# Audio_connector_breakout.net
KiCad netlist of a schematic drawn in EasyEDA
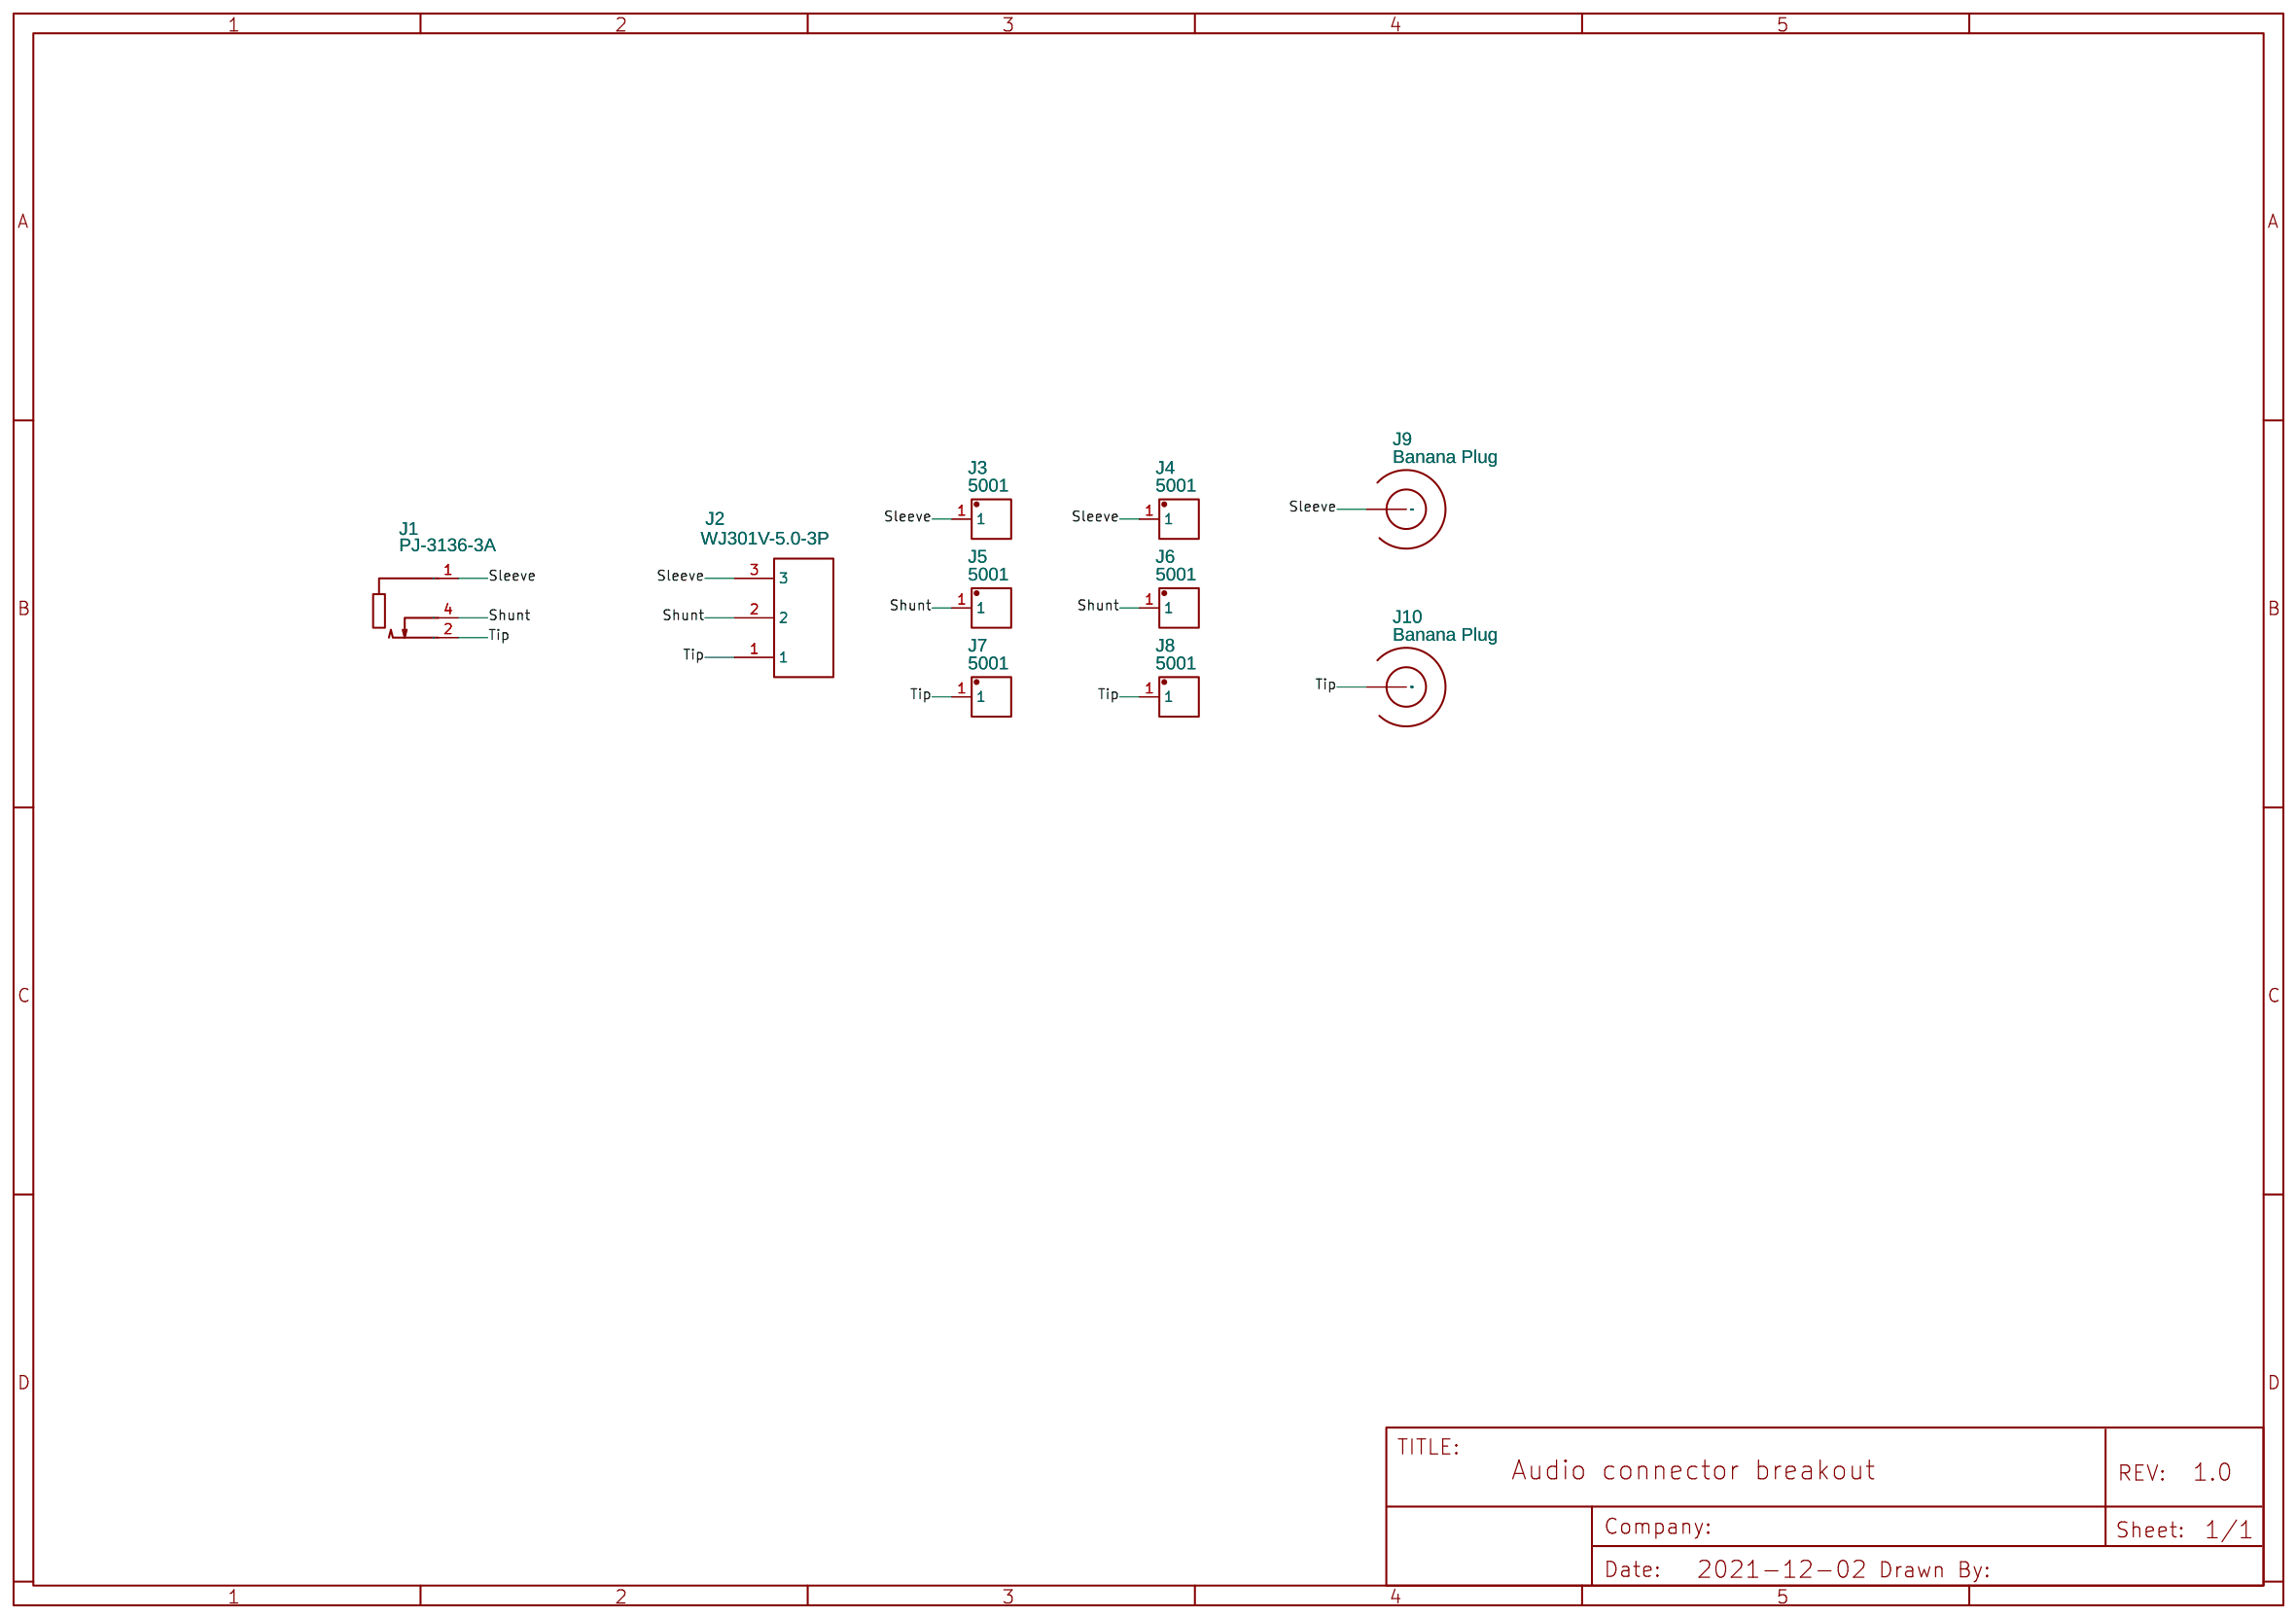
[diagram p0: schematic sheet]

(export (version "E")
  (design (tool "Eeschema 10.0.6"))
  (components
    (comp (ref "J1")
      (value "PJ-3136-3A")
      (fields (field (name "BOM_Supplier Part") "C707248"))
      (libsource (lib "") (part "PJ-3136-3A"))
    )
    (comp (ref "J2")
      (value "WJ301V-5.0-3P")
      (fields (field (name "BOM_Supplier Part") "C8483"))
      (libsource (lib "") (part "WJ301V-5.0-3P"))
    )
    (comp (ref "J3")
      (value "5001")
      (fields (field (name "BOM_Supplier Part") "C238122"))
      (libsource (lib "") (part "5001"))
    )
    (comp (ref "J4")
      (value "5001")
      (fields (field (name "BOM_Supplier Part") "C238122"))
      (libsource (lib "") (part "5001"))
    )
    (comp (ref "J5")
      (value "5001")
      (fields (field (name "BOM_Supplier Part") "C238122"))
      (libsource (lib "") (part "5001"))
    )
    (comp (ref "J6")
      (value "5001")
      (fields (field (name "BOM_Supplier Part") "C238122"))
      (libsource (lib "") (part "5001"))
    )
    (comp (ref "J7")
      (value "5001")
      (fields (field (name "BOM_Supplier Part") "C238122"))
      (libsource (lib "") (part "5001"))
    )
    (comp (ref "J8")
      (value "5001")
      (fields (field (name "BOM_Supplier Part") "C238122"))
      (libsource (lib "") (part "5001"))
    )
    (comp (ref "J9")
      (value "Banana Plug")
      (fields (field (name "BOM_Manufacturer Part") "24.247.2") (field (name "BOM_Supplier Part") "169-8951"))
      (libsource (lib "") (part "Banana Plug"))
    )
    (comp (ref "J10")
      (value "Banana Plug")
      (fields (field (name "BOM_Manufacturer Part") "24.247.2") (field (name "BOM_Supplier Part") "169-8951"))
      (libsource (lib "") (part "Banana Plug"))
    )
  )
  (nets
    (net (code "1") (name "/Shunt") (class "Default")
      (node (ref "J1") (pin "4") (pinfunction "4_4") (pintype "unspecified"))
      (node (ref "J2") (pin "2") (pinfunction "2_2") (pintype "unspecified"))
      (node (ref "J5") (pin "1") (pinfunction "1_1") (pintype "unspecified"))
      (node (ref "J6") (pin "1") (pinfunction "1_1") (pintype "unspecified"))
    )
    (net (code "2") (name "/Sleeve") (class "Default")
      (node (ref "J1") (pin "1") (pinfunction "1_1") (pintype "unspecified"))
      (node (ref "J2") (pin "3") (pinfunction "3_3") (pintype "unspecified"))
      (node (ref "J3") (pin "1") (pinfunction "1_1") (pintype "unspecified"))
      (node (ref "J4") (pin "1") (pinfunction "1_1") (pintype "unspecified"))
      (node (ref "J9") (pin "1") (pinfunction "Banana_Plug_1") (pintype "unspecified"))
    )
    (net (code "3") (name "/Tip") (class "Default")
      (node (ref "J1") (pin "2") (pinfunction "2_2") (pintype "unspecified"))
      (node (ref "J10") (pin "1") (pinfunction "Banana_Plug_1") (pintype "unspecified"))
      (node (ref "J2") (pin "1") (pinfunction "1_1") (pintype "unspecified"))
      (node (ref "J7") (pin "1") (pinfunction "1_1") (pintype "unspecified"))
      (node (ref "J8") (pin "1") (pinfunction "1_1") (pintype "unspecified"))
    )
  )
)
